# Front_Node_Terminal_Blocks.net
KiCad netlist of a schematic drawn in EAGLE
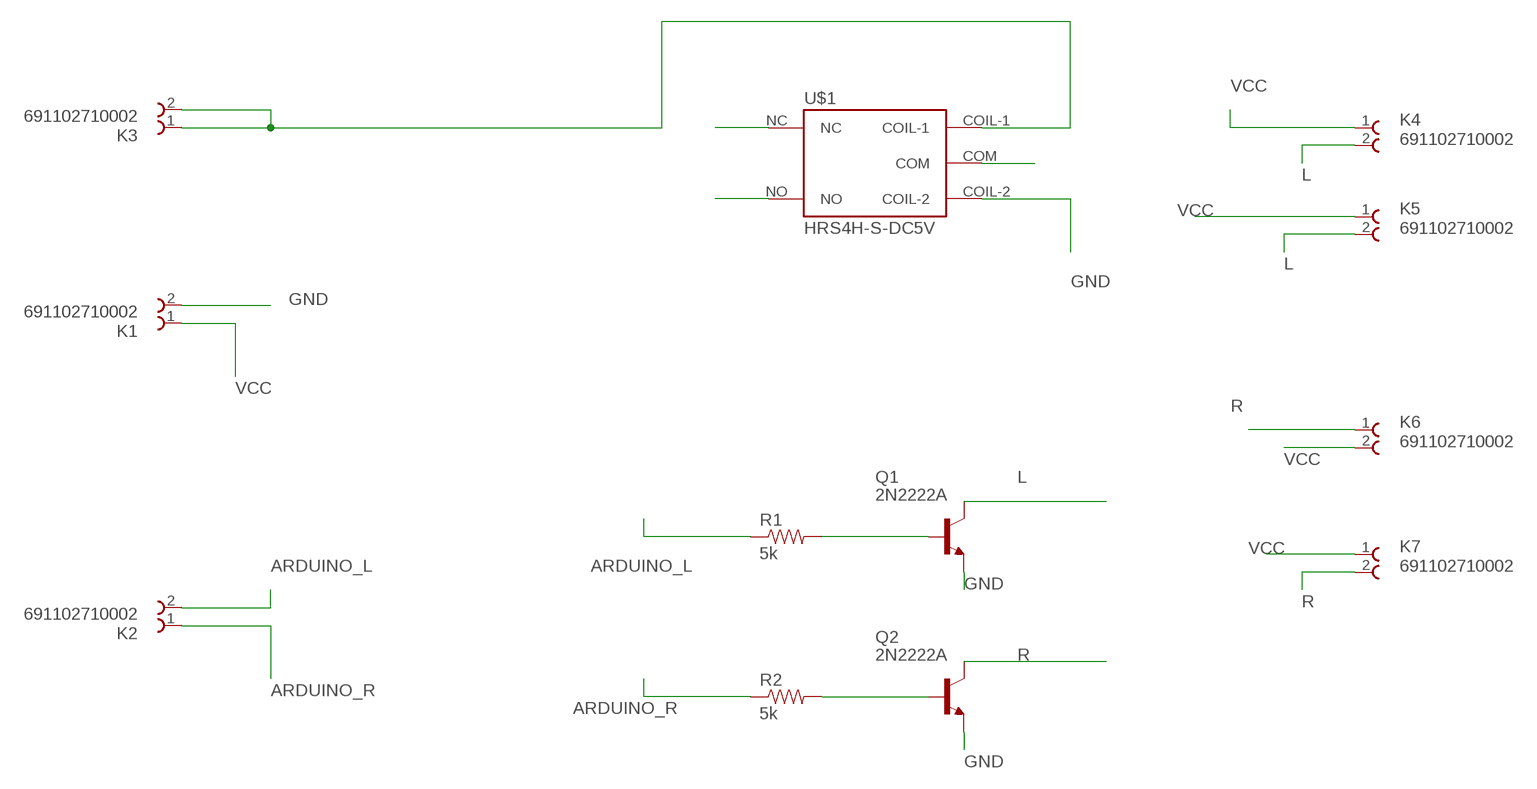
[diagram p0: schematic, sheet 1]

(export (version "E")
  (design (tool "Eeschema 10.0.6"))
  (components
    (comp (ref "K1")
      (value "691102710002")
      (footprint "eagle-import:691102710002")
      (libsource (lib "eagle-import") (part "691102710002"))
    )
    (comp (ref "K2")
      (value "691102710002")
      (footprint "eagle-import:691102710002")
      (libsource (lib "eagle-import") (part "691102710002"))
    )
    (comp (ref "K3")
      (value "691102710002")
      (footprint "eagle-import:691102710002")
      (libsource (lib "eagle-import") (part "691102710002"))
    )
    (comp (ref "K4")
      (value "691102710002")
      (footprint "eagle-import:691102710002")
      (libsource (lib "eagle-import") (part "691102710002"))
    )
    (comp (ref "K5")
      (value "691102710002")
      (footprint "eagle-import:691102710002")
      (libsource (lib "eagle-import") (part "691102710002"))
    )
    (comp (ref "K6")
      (value "691102710002")
      (footprint "eagle-import:691102710002")
      (libsource (lib "eagle-import") (part "691102710002"))
    )
    (comp (ref "K7")
      (value "691102710002")
      (footprint "eagle-import:691102710002")
      (libsource (lib "eagle-import") (part "691102710002"))
    )
    (comp (ref "Q1")
      (value "2N2222A")
      (footprint "eagle-import:TO18")
      (libsource (lib "eagle-import") (part "2N2222A"))
    )
    (comp (ref "Q2")
      (value "2N2222A")
      (footprint "eagle-import:TO18")
      (libsource (lib "eagle-import") (part "2N2222A"))
    )
    (comp (ref "R1")
      (value "5k")
      (footprint "eagle-import:AXIAL-0.4")
      (libsource (lib "eagle-import") (part "RESISTORPTH-1/4W"))
    )
    (comp (ref "R2")
      (value "5k")
      (footprint "eagle-import:AXIAL-0.4")
      (libsource (lib "eagle-import") (part "RESISTORPTH-1/4W"))
    )
    (comp (ref "U$1")
      (value "HRS4H-S-DC5V")
      (footprint "eagle-import:RELAY")
      (libsource (lib "eagle-import") (part "HRS4H-S-DC5V"))
    )
  )
  (nets
    (net (code "1") (name "/ARDUINO_L") (class "Default")
      (node (ref "K2") (pin "2") (pinfunction "2_2") (pintype "passive"))
      (node (ref "R1") (pin "P$1") (pinfunction "1_P$1") (pintype "passive"))
    )
    (net (code "2") (name "/ARDUINO_R") (class "Default")
      (node (ref "K2") (pin "1") (pinfunction "1_1") (pintype "passive"))
      (node (ref "R2") (pin "P$1") (pinfunction "1_P$1") (pintype "passive"))
    )
    (net (code "3") (name "/GND") (class "Default")
      (node (ref "K1") (pin "2") (pinfunction "2_2") (pintype "passive"))
      (node (ref "Q1") (pin "1") (pinfunction "E_1") (pintype "passive"))
      (node (ref "Q2") (pin "1") (pinfunction "E_1") (pintype "passive"))
      (node (ref "U$1") (pin "COIL-2") (pinfunction "COIL-2_COIL-2") (pintype "power_in"))
    )
    (net (code "4") (name "/L") (class "Default")
      (node (ref "K4") (pin "2") (pinfunction "2_2") (pintype "passive"))
      (node (ref "K5") (pin "2") (pinfunction "2_2") (pintype "passive"))
      (node (ref "Q1") (pin "3") (pinfunction "C_3") (pintype "passive"))
    )
    (net (code "5") (name "/R") (class "Default")
      (node (ref "K6") (pin "1") (pinfunction "1_1") (pintype "passive"))
      (node (ref "K7") (pin "2") (pinfunction "2_2") (pintype "passive"))
      (node (ref "Q2") (pin "3") (pinfunction "C_3") (pintype "passive"))
    )
    (net (code "6") (name "/VCC") (class "Default")
      (node (ref "K1") (pin "1") (pinfunction "1_1") (pintype "passive"))
      (node (ref "K4") (pin "1") (pinfunction "1_1") (pintype "passive"))
      (node (ref "K5") (pin "1") (pinfunction "1_1") (pintype "passive"))
      (node (ref "K6") (pin "2") (pinfunction "2_2") (pintype "passive"))
      (node (ref "K7") (pin "1") (pinfunction "1_1") (pintype "passive"))
    )
    (net (code "7") (name "Net-(K3-Pad1)") (class "Default")
      (node (ref "K3") (pin "1") (pinfunction "1_1") (pintype "passive"))
      (node (ref "K3") (pin "2") (pinfunction "2_2") (pintype "passive"))
      (node (ref "U$1") (pin "COIL-1") (pinfunction "COIL-1_COIL-1") (pintype "power_in"))
    )
    (net (code "8") (name "Net-(Q1-B)") (class "Default")
      (node (ref "Q1") (pin "2") (pinfunction "B_2") (pintype "passive"))
      (node (ref "R1") (pin "P$2") (pinfunction "2_P$2") (pintype "passive"))
    )
    (net (code "9") (name "Net-(Q2-B)") (class "Default")
      (node (ref "Q2") (pin "2") (pinfunction "B_2") (pintype "passive"))
      (node (ref "R2") (pin "P$2") (pinfunction "2_P$2") (pintype "passive"))
    )
    (net (code "10") (name "unconnected-(U$1-PadCOM)") (class "Default")
      (node (ref "U$1") (pin "COM") (pinfunction "COM_COM") (pintype "bidirectional"))
    )
    (net (code "11") (name "unconnected-(U$1-PadNC)") (class "Default")
      (node (ref "U$1") (pin "NC") (pinfunction "NC_NC") (pintype "bidirectional"))
    )
    (net (code "12") (name "unconnected-(U$1-PadNO)") (class "Default")
      (node (ref "U$1") (pin "NO") (pinfunction "NO_NO") (pintype "bidirectional"))
    )
  )
)
